# Main.net
KiCad netlist of a schematic drawn in Altium Designer
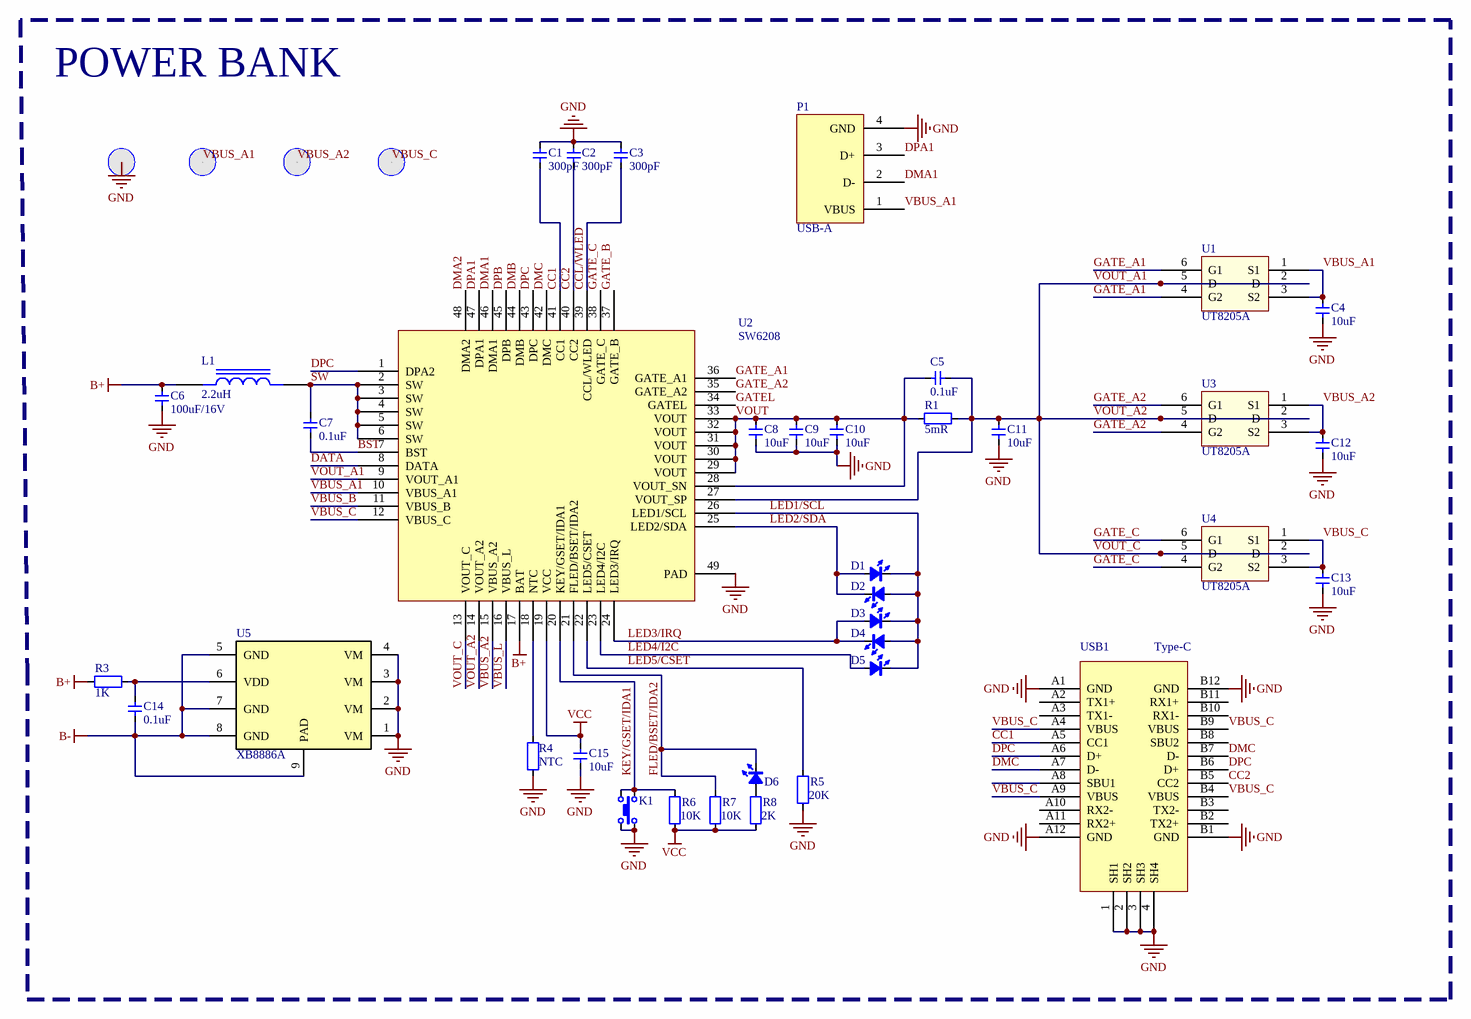
[diagram p0: Main.SchDoc]

(export (version "E")
  (design (tool "Eeschema 10.0.6"))
  (components
    (comp (ref "C1")
      (value "300pF")
      (footprint "XG_电容(SMC):0805C")
      (description "Capacitor")
      (libsource (lib "MyPcbLib") (part "电容-0402"))
    )
    (comp (ref "C2")
      (value "300pF")
      (footprint "XG_电容(SMC):0805C")
      (description "Capacitor")
      (libsource (lib "MyPcbLib") (part "电容-0402"))
    )
    (comp (ref "C3")
      (value "300pF")
      (footprint "XG_电容(SMC):0805C")
      (description "Capacitor")
      (libsource (lib "MyPcbLib") (part "电容-0402"))
    )
    (comp (ref "C4")
      (value "10uF")
      (footprint "SW6208Power_Bank:0603-CAP")
      (description "Capacitor")
      (libsource (lib "MyPcbLib") (part "电容-0603"))
    )
    (comp (ref "C5")
      (value "0.1uF")
      (footprint "XG_电容(SMC):0805C")
      (description "Capacitor")
      (libsource (lib "MyPcbLib") (part "电容-0402"))
    )
    (comp (ref "C6")
      (value "100uF/16V")
      (footprint "SW6208Power_Bank:1206-CAP")
      (description "Capacitor")
      (libsource (lib "MyPcbLib") (part "电容-1206"))
    )
    (comp (ref "C7")
      (value "0.1uF")
      (footprint "XG_电容(SMC):0805C")
      (description "Capacitor")
      (libsource (lib "MyPcbLib") (part "电容-0402"))
    )
    (comp (ref "C8")
      (value "10uF")
      (footprint "SW6208Power_Bank:0603-CAP")
      (description "Capacitor")
      (libsource (lib "MyPcbLib") (part "电容-0603"))
    )
    (comp (ref "C9")
      (value "10uF")
      (footprint "SW6208Power_Bank:0603-CAP")
      (description "Capacitor")
      (libsource (lib "MyPcbLib") (part "电容-0603"))
    )
    (comp (ref "C10")
      (value "10uF")
      (footprint "SW6208Power_Bank:0603-CAP")
      (description "Capacitor")
      (libsource (lib "MyPcbLib") (part "电容-0603"))
    )
    (comp (ref "C11")
      (value "10uF")
      (footprint "SW6208Power_Bank:0603-CAP")
      (description "Capacitor")
      (libsource (lib "MyPcbLib") (part "电容-0603"))
    )
    (comp (ref "C12")
      (value "10uF")
      (footprint "SW6208Power_Bank:0603-CAP")
      (description "Capacitor")
      (libsource (lib "MyPcbLib") (part "电容-0603"))
    )
    (comp (ref "C13")
      (value "10uF")
      (footprint "SW6208Power_Bank:0603-CAP")
      (description "Capacitor")
      (libsource (lib "MyPcbLib") (part "电容-0603"))
    )
    (comp (ref "C14")
      (value "0.1uF")
      (footprint "XG_电容(SMC):0805C")
      (description "Capacitor")
      (libsource (lib "MyPcbLib") (part "电容-0402"))
    )
    (comp (ref "C15")
      (value "10uF")
      (footprint "SW6208Power_Bank:0603-CAP")
      (description "Capacitor")
      (libsource (lib "MyPcbLib") (part "电容-0603"))
    )
    (comp (ref "D1")
      (value "color?")
      (footprint "XG_LED:LED0805R")
      (description "LED")
      (libsource (lib "KitSprout") (part "LED_0402"))
    )
    (comp (ref "D2")
      (value "color?")
      (footprint "XG_LED:LED0805R")
      (description "LED")
      (libsource (lib "") (part "LED_0402_1"))
    )
    (comp (ref "D3")
      (value "color?")
      (footprint "XG_LED:LED0805R")
      (description "LED")
      (libsource (lib "KitSprout") (part "LED_0402"))
    )
    (comp (ref "D4")
      (value "color?")
      (footprint "XG_LED:LED0805R")
      (description "LED")
      (libsource (lib "") (part "LED_0402_1"))
    )
    (comp (ref "D5")
      (value "color?")
      (footprint "XG_LED:LED0805R")
      (description "LED")
      (libsource (lib "KitSprout") (part "LED_0402"))
    )
    (comp (ref "D6")
      (value "color?")
      (footprint "XG_LED:LED0805R")
      (description "LED")
      (libsource (lib "") (part "LED_0402_2"))
    )
    (comp (ref "K1")
      (value "TACT 4P")
      (footprint "SW6208Power_Bank:ButtonTACT_3.5*3.55_90")
      (description "Button")
      (libsource (lib "KitSprout") (part "ButtonTACT"))
    )
    (comp (ref "L1")
      (value "2.2uH")
      (footprint "SW6208Power_Bank:IND_1040")
      (description "Fixed Inductors 4.7uH 30% SMD 1240")
      (fields (field (name "MF") "Bourns") (field (name "MP") "SRR1240-4R7Y"))
      (libsource (lib "mLib") (part "电感-1040"))
    )
    (comp (ref "P1")
      (value "USB-A")
      (footprint "SW6208Power_Bank:USB-Short")
      (libsource (lib "MyPcbLib") (part "USB-A"))
    )
    (comp (ref "R1")
      (value "5mR")
      (footprint "SW6208Power_Bank:1206-RES")
      (description "Resistor")
      (libsource (lib "MyPcbLib") (part "电阻-1206"))
    )
    (comp (ref "R3")
      (value "1K")
      (footprint "XG_电阻(SMC):0805R")
      (description "Resistor")
      (libsource (lib "") (part "电阻-0402_1"))
    )
    (comp (ref "R4")
      (value "NTC")
      (footprint "SW6208Power_Bank:0805-L")
      (description "Resistor")
      (libsource (lib "MyPcbLib") (part "电阻-0805"))
    )
    (comp (ref "R5")
      (value "20K")
      (footprint "XG_电阻(SMC):0805R")
      (description "Resistor")
      (libsource (lib "MyPcbLib") (part "电阻-0402"))
    )
    (comp (ref "R6")
      (value "10K")
      (footprint "XG_电阻(SMC):0805R")
      (description "Resistor")
      (libsource (lib "MyPcbLib") (part "电阻-0402"))
    )
    (comp (ref "R7")
      (value "10K")
      (footprint "XG_电阻(SMC):0805R")
      (description "Resistor")
      (libsource (lib "MyPcbLib") (part "电阻-0402"))
    )
    (comp (ref "R8")
      (value "2K")
      (footprint "XG_电阻(SMC):0805R")
      (description "Resistor")
      (libsource (lib "MyPcbLib") (part "电阻-0402"))
    )
    (comp (ref "T1")
      (value "测试点")
      (footprint "SW6208Power_Bank:TEST_PT")
      (libsource (lib "MyPcbLib") (part "测试点"))
    )
    (comp (ref "T2")
      (value "测试点")
      (footprint "SW6208Power_Bank:TEST_PT")
      (libsource (lib "MyPcbLib") (part "测试点"))
    )
    (comp (ref "T3")
      (value "测试点")
      (footprint "SW6208Power_Bank:TEST_PT")
      (libsource (lib "MyPcbLib") (part "测试点"))
    )
    (comp (ref "T4")
      (value "测试点")
      (footprint "SW6208Power_Bank:TEST_PT")
      (libsource (lib "MyPcbLib") (part "测试点"))
    )
    (comp (ref "U1")
      (value "UT8205A")
      (footprint "SW6208Power_Bank:SOT23-6")
      (libsource (lib "mLib") (part "UT8205A"))
    )
    (comp (ref "U2")
      (value "SW6208")
      (footprint "SW6208Power_Bank:QFN-48_6x6")
      (description "充电宝芯片")
      (libsource (lib "mLib") (part "SW6208"))
    )
    (comp (ref "U3")
      (value "UT8205A")
      (footprint "SW6208Power_Bank:SOT23-6")
      (libsource (lib "mLib") (part "UT8205A"))
    )
    (comp (ref "U4")
      (value "UT8205A")
      (footprint "SW6208Power_Bank:SOT23-6")
      (libsource (lib "mLib") (part "UT8205A"))
    )
    (comp (ref "U5")
      (value "XB8886A")
      (footprint "SW6208Power_Bank:SO-8-PAD")
      (fields (field (name "MF") "Texas Instruments") (field (name "MP") "NE5532D"))
      (libsource (lib "mLib") (part "XB8886A"))
    )
    (comp (ref "USB1")
      (value "Type-C")
      (footprint "SW6208Power_Bank:Type-C-TOP")
      (libsource (lib "MyPcbLib") (part "USB-Type-C-TOP"))
    )
  )
  (nets
    (net (code "1") (name "/BST") (class "Default")
      (node (ref "C7") (pin "2") (pinfunction "2_2") (pintype "passive"))
      (node (ref "U2") (pin "7") (pinfunction "BST_7") (pintype "passive"))
    )
    (net (code "2") (name "/CC1") (class "Default")
      (node (ref "C1") (pin "2") (pinfunction "2_2") (pintype "passive"))
      (node (ref "U2") (pin "41") (pinfunction "CC1_41") (pintype "passive"))
      (node (ref "USB1") (pin "A5") (pinfunction "CC1_A5") (pintype "passive"))
    )
    (net (code "3") (name "/CC2") (class "Default")
      (node (ref "C2") (pin "2") (pinfunction "2_2") (pintype "passive"))
      (node (ref "U2") (pin "40") (pinfunction "CC2_40") (pintype "passive"))
      (node (ref "USB1") (pin "B5") (pinfunction "CC2_B5") (pintype "passive"))
    )
    (net (code "4") (name "/CCL{slash}WLED") (class "Default")
      (node (ref "C3") (pin "2") (pinfunction "2_2") (pintype "passive"))
      (node (ref "U2") (pin "39") (pinfunction "CCL/WLED_39") (pintype "passive"))
    )
    (net (code "5") (name "/DATA") (class "Default")
      (node (ref "U2") (pin "8") (pinfunction "DATA_8") (pintype "passive"))
    )
    (net (code "6") (name "/DMA1") (class "Default")
      (node (ref "P1") (pin "2") (pinfunction "D-_2") (pintype "passive"))
      (node (ref "U2") (pin "46") (pinfunction "DMA1_46") (pintype "passive"))
    )
    (net (code "7") (name "/DMA2") (class "Default")
      (node (ref "U2") (pin "48") (pinfunction "DMA2_48") (pintype "passive"))
    )
    (net (code "8") (name "/DMB") (class "Default")
      (node (ref "U2") (pin "44") (pinfunction "DMB_44") (pintype "passive"))
    )
    (net (code "9") (name "/DMC") (class "Default")
      (node (ref "U2") (pin "42") (pinfunction "DMC_42") (pintype "passive"))
      (node (ref "USB1") (pin "A7") (pinfunction "D-_A7") (pintype "passive"))
      (node (ref "USB1") (pin "B7") (pinfunction "D-_B7") (pintype "passive"))
    )
    (net (code "10") (name "/DPA1") (class "Default")
      (node (ref "P1") (pin "3") (pinfunction "D+_3") (pintype "passive"))
      (node (ref "U2") (pin "47") (pinfunction "DPA1_47") (pintype "passive"))
    )
    (net (code "11") (name "/DPB") (class "Default")
      (node (ref "U2") (pin "45") (pinfunction "DPB_45") (pintype "passive"))
    )
    (net (code "12") (name "/DPC") (class "Default")
      (node (ref "U2") (pin "1") (pinfunction "DPA2_1") (pintype "passive"))
      (node (ref "U2") (pin "43") (pinfunction "DPC_43") (pintype "passive"))
      (node (ref "USB1") (pin "A6") (pinfunction "D+_A6") (pintype "passive"))
      (node (ref "USB1") (pin "B6") (pinfunction "D+_B6") (pintype "passive"))
    )
    (net (code "13") (name "/FLED{slash}BSET{slash}IDA2") (class "Default")
      (node (ref "D6") (pin "2") (pinfunction "K_2") (pintype "passive"))
      (node (ref "R7") (pin "1") (pinfunction "1_1") (pintype "passive"))
      (node (ref "U2") (pin "21") (pinfunction "FLED/BSET/IDA2_21") (pintype "passive"))
    )
    (net (code "14") (name "/GATEL") (class "Default")
      (node (ref "U2") (pin "34") (pinfunction "GATEL_34") (pintype "passive"))
    )
    (net (code "15") (name "/GATE_A1") (class "Default")
      (node (ref "U1") (pin "4") (pinfunction "G2_4") (pintype "passive"))
      (node (ref "U1") (pin "6") (pinfunction "G1_6") (pintype "passive"))
      (node (ref "U2") (pin "36") (pinfunction "GATE_A1_36") (pintype "passive"))
    )
    (net (code "16") (name "/GATE_A2") (class "Default")
      (node (ref "U2") (pin "35") (pinfunction "GATE_A2_35") (pintype "passive"))
      (node (ref "U3") (pin "4") (pinfunction "G2_4") (pintype "passive"))
      (node (ref "U3") (pin "6") (pinfunction "G1_6") (pintype "passive"))
    )
    (net (code "17") (name "/GATE_B") (class "Default")
      (node (ref "U2") (pin "37") (pinfunction "GATE_B_37") (pintype "passive"))
    )
    (net (code "18") (name "/GATE_C") (class "Default")
      (node (ref "U2") (pin "38") (pinfunction "GATE_C_38") (pintype "passive"))
      (node (ref "U4") (pin "4") (pinfunction "G2_4") (pintype "passive"))
      (node (ref "U4") (pin "6") (pinfunction "G1_6") (pintype "passive"))
    )
    (net (code "19") (name "/KEY{slash}GSET{slash}IDA1") (class "Default")
      (node (ref "K1") (pin "2") (pinfunction "2_2") (pintype "passive"))
      (node (ref "K1") (pin "4") (pinfunction "4_4") (pintype "passive"))
      (node (ref "R6") (pin "1") (pinfunction "1_1") (pintype "passive"))
      (node (ref "U2") (pin "20") (pinfunction "KEY/GSET/IDA1_20") (pintype "passive"))
    )
    (net (code "20") (name "/LED1{slash}SCL") (class "Default")
      (node (ref "D1") (pin "2") (pinfunction "K_2") (pintype "passive"))
      (node (ref "D2") (pin "1") (pinfunction "A_1") (pintype "passive"))
      (node (ref "D3") (pin "2") (pinfunction "K_2") (pintype "passive"))
      (node (ref "D4") (pin "1") (pinfunction "A_1") (pintype "passive"))
      (node (ref "D5") (pin "2") (pinfunction "K_2") (pintype "passive"))
      (node (ref "U2") (pin "26") (pinfunction "LED1/SCL_26") (pintype "passive"))
    )
    (net (code "21") (name "/LED2{slash}SDA") (class "Default")
      (node (ref "D1") (pin "1") (pinfunction "A_1") (pintype "passive"))
      (node (ref "D2") (pin "2") (pinfunction "K_2") (pintype "passive"))
      (node (ref "U2") (pin "25") (pinfunction "LED2/SDA_25") (pintype "passive"))
    )
    (net (code "22") (name "/LED3{slash}IRQ") (class "Default")
      (node (ref "D3") (pin "1") (pinfunction "A_1") (pintype "passive"))
      (node (ref "D4") (pin "2") (pinfunction "K_2") (pintype "passive"))
      (node (ref "U2") (pin "24") (pinfunction "LED3/IRQ_24") (pintype "passive"))
    )
    (net (code "23") (name "/LED4{slash}I2C") (class "Default")
      (node (ref "D5") (pin "1") (pinfunction "A_1") (pintype "passive"))
      (node (ref "U2") (pin "23") (pinfunction "LED4/I2C_23") (pintype "passive"))
    )
    (net (code "24") (name "/LED5{slash}CSET") (class "Default")
      (node (ref "R5") (pin "1") (pinfunction "1_1") (pintype "passive"))
      (node (ref "U2") (pin "22") (pinfunction "LED5/CSET_22") (pintype "passive"))
    )
    (net (code "25") (name "/SW") (class "Default")
      (node (ref "C7") (pin "1") (pinfunction "1_1") (pintype "passive"))
      (node (ref "L1") (pin "2") (pinfunction "2_2") (pintype "passive"))
      (node (ref "U2") (pin "2") (pinfunction "SW_2") (pintype "passive"))
      (node (ref "U2") (pin "3") (pinfunction "SW_3") (pintype "passive"))
      (node (ref "U2") (pin "4") (pinfunction "SW_4") (pintype "passive"))
      (node (ref "U2") (pin "5") (pinfunction "SW_5") (pintype "passive"))
      (node (ref "U2") (pin "6") (pinfunction "SW_6") (pintype "passive"))
    )
    (net (code "26") (name "/VBUS_A1") (class "Default")
      (node (ref "C4") (pin "2") (pinfunction "2_2") (pintype "passive"))
      (node (ref "P1") (pin "1") (pinfunction "VBUS_1") (pintype "passive"))
      (node (ref "T2") (pin "0") (pinfunction "0_0") (pintype "passive"))
      (node (ref "U1") (pin "1") (pinfunction "S1_1") (pintype "passive"))
      (node (ref "U1") (pin "3") (pinfunction "S2_3") (pintype "passive"))
      (node (ref "U2") (pin "10") (pinfunction "VBUS_A1_10") (pintype "passive"))
    )
    (net (code "27") (name "/VBUS_A2") (class "Default")
      (node (ref "C12") (pin "2") (pinfunction "2_2") (pintype "passive"))
      (node (ref "T3") (pin "0") (pinfunction "0_0") (pintype "passive"))
      (node (ref "U2") (pin "15") (pinfunction "VBUS_A2_15") (pintype "passive"))
      (node (ref "U3") (pin "1") (pinfunction "S1_1") (pintype "passive"))
      (node (ref "U3") (pin "3") (pinfunction "S2_3") (pintype "passive"))
    )
    (net (code "28") (name "/VBUS_B") (class "Default")
      (node (ref "U2") (pin "11") (pinfunction "VBUS_B_11") (pintype "passive"))
    )
    (net (code "29") (name "/VBUS_C") (class "Default")
      (node (ref "C13") (pin "2") (pinfunction "2_2") (pintype "passive"))
      (node (ref "T4") (pin "0") (pinfunction "0_0") (pintype "passive"))
      (node (ref "U2") (pin "12") (pinfunction "VBUS_C_12") (pintype "passive"))
      (node (ref "U4") (pin "1") (pinfunction "S1_1") (pintype "passive"))
      (node (ref "U4") (pin "3") (pinfunction "S2_3") (pintype "passive"))
      (node (ref "USB1") (pin "A4") (pinfunction "VBUS_A4") (pintype "passive"))
      (node (ref "USB1") (pin "A9") (pinfunction "VBUS_A9") (pintype "passive"))
      (node (ref "USB1") (pin "B4") (pinfunction "VBUS_B4") (pintype "passive"))
      (node (ref "USB1") (pin "B9") (pinfunction "VBUS_B9") (pintype "passive"))
    )
    (net (code "30") (name "/VBUS_L") (class "Default")
      (node (ref "U2") (pin "16") (pinfunction "VBUS_L_16") (pintype "passive"))
    )
    (net (code "31") (name "/VOUT") (class "Default")
      (node (ref "C10") (pin "2") (pinfunction "2_2") (pintype "passive"))
      (node (ref "C5") (pin "1") (pinfunction "1_1") (pintype "passive"))
      (node (ref "C8") (pin "2") (pinfunction "2_2") (pintype "passive"))
      (node (ref "C9") (pin "2") (pinfunction "2_2") (pintype "passive"))
      (node (ref "R1") (pin "1") (pinfunction "1_1") (pintype "passive"))
      (node (ref "U2") (pin "28") (pinfunction "VOUT_SN_28") (pintype "passive"))
      (node (ref "U2") (pin "29") (pinfunction "VOUT_29") (pintype "passive"))
      (node (ref "U2") (pin "30") (pinfunction "VOUT_30") (pintype "passive"))
      (node (ref "U2") (pin "31") (pinfunction "VOUT_31") (pintype "passive"))
      (node (ref "U2") (pin "32") (pinfunction "VOUT_32") (pintype "passive"))
      (node (ref "U2") (pin "33") (pinfunction "VOUT_33") (pintype "passive"))
    )
    (net (code "32") (name "/VOUT_A1") (class "Default")
      (node (ref "C11") (pin "2") (pinfunction "2_2") (pintype "passive"))
      (node (ref "C5") (pin "2") (pinfunction "2_2") (pintype "passive"))
      (node (ref "R1") (pin "2") (pinfunction "2_2") (pintype "passive"))
      (node (ref "U1") (pin "2") (pinfunction "D_2") (pintype "passive"))
      (node (ref "U1") (pin "5") (pinfunction "D_5") (pintype "passive"))
      (node (ref "U2") (pin "13") (pinfunction "VOUT_C_13") (pintype "passive"))
      (node (ref "U2") (pin "14") (pinfunction "VOUT_A2_14") (pintype "passive"))
      (node (ref "U2") (pin "27") (pinfunction "VOUT_SP_27") (pintype "passive"))
      (node (ref "U2") (pin "9") (pinfunction "VOUT_A1_9") (pintype "passive"))
      (node (ref "U3") (pin "2") (pinfunction "D_2") (pintype "passive"))
      (node (ref "U3") (pin "5") (pinfunction "D_5") (pintype "passive"))
      (node (ref "U4") (pin "2") (pinfunction "D_2") (pintype "passive"))
      (node (ref "U4") (pin "5") (pinfunction "D_5") (pintype "passive"))
    )
    (net (code "33") (name "B+") (class "Default")
      (node (ref "C6") (pin "2") (pinfunction "2_2") (pintype "passive"))
      (node (ref "L1") (pin "1") (pinfunction "1_1") (pintype "passive"))
      (node (ref "R3") (pin "2") (pinfunction "2_2") (pintype "passive"))
      (node (ref "U2") (pin "17") (pinfunction "BAT_17") (pintype "passive"))
    )
    (net (code "34") (name "B-") (class "Default")
      (node (ref "C14") (pin "2") (pinfunction "2_2") (pintype "passive"))
      (node (ref "U5") (pin "5") (pinfunction "GND_5") (pintype "passive"))
      (node (ref "U5") (pin "7") (pinfunction "GND_7") (pintype "passive"))
      (node (ref "U5") (pin "8") (pinfunction "GND_8") (pintype "passive"))
      (node (ref "U5") (pin "9") (pinfunction "PAD_9") (pintype "passive"))
    )
    (net (code "35") (name "GND") (class "Default")
      (node (ref "C1") (pin "1") (pinfunction "1_1") (pintype "passive"))
      (node (ref "C10") (pin "1") (pinfunction "1_1") (pintype "passive"))
      (node (ref "C11") (pin "1") (pinfunction "1_1") (pintype "passive"))
      (node (ref "C12") (pin "1") (pinfunction "1_1") (pintype "passive"))
      (node (ref "C13") (pin "1") (pinfunction "1_1") (pintype "passive"))
      (node (ref "C15") (pin "1") (pinfunction "1_1") (pintype "passive"))
      (node (ref "C2") (pin "1") (pinfunction "1_1") (pintype "passive"))
      (node (ref "C3") (pin "1") (pinfunction "1_1") (pintype "passive"))
      (node (ref "C4") (pin "1") (pinfunction "1_1") (pintype "passive"))
      (node (ref "C6") (pin "1") (pinfunction "1_1") (pintype "passive"))
      (node (ref "C8") (pin "1") (pinfunction "1_1") (pintype "passive"))
      (node (ref "C9") (pin "1") (pinfunction "1_1") (pintype "passive"))
      (node (ref "K1") (pin "1") (pinfunction "1_1") (pintype "passive"))
      (node (ref "K1") (pin "3") (pinfunction "3_3") (pintype "passive"))
      (node (ref "P1") (pin "4") (pinfunction "GND_4") (pintype "passive"))
      (node (ref "R4") (pin "1") (pinfunction "1_1") (pintype "passive"))
      (node (ref "R5") (pin "2") (pinfunction "2_2") (pintype "passive"))
      (node (ref "T1") (pin "0") (pinfunction "0_0") (pintype "passive"))
      (node (ref "U2") (pin "49") (pinfunction "PAD_49") (pintype "passive"))
      (node (ref "U5") (pin "1") (pinfunction "VM_1") (pintype "passive"))
      (node (ref "U5") (pin "2") (pinfunction "VM_2") (pintype "passive"))
      (node (ref "U5") (pin "3") (pinfunction "VM_3") (pintype "passive"))
      (node (ref "U5") (pin "4") (pinfunction "VM_4") (pintype "passive"))
      (node (ref "USB1") (pin "1") (pinfunction "SH1_1") (pintype "passive"))
      (node (ref "USB1") (pin "2") (pinfunction "SH2_2") (pintype "passive"))
      (node (ref "USB1") (pin "3") (pinfunction "SH3_3") (pintype "passive"))
      (node (ref "USB1") (pin "4") (pinfunction "SH4_4") (pintype "passive"))
      (node (ref "USB1") (pin "A1") (pinfunction "GND_A1") (pintype "passive"))
      (node (ref "USB1") (pin "A12") (pinfunction "GND_A12") (pintype "passive"))
      (node (ref "USB1") (pin "B1") (pinfunction "GND_B1") (pintype "passive"))
      (node (ref "USB1") (pin "B12") (pinfunction "GND_B12") (pintype "passive"))
    )
    (net (code "36") (name "Net-(D6-A)") (class "Default")
      (node (ref "D6") (pin "1") (pinfunction "A_1") (pintype "passive"))
      (node (ref "R8") (pin "1") (pinfunction "1_1") (pintype "passive"))
    )
    (net (code "37") (name "Net-(U2-NTC)") (class "Default")
      (node (ref "R4") (pin "2") (pinfunction "2_2") (pintype "passive"))
      (node (ref "U2") (pin "18") (pinfunction "NTC_18") (pintype "passive"))
    )
    (net (code "38") (name "Net-(U5-VDD)") (class "Default")
      (node (ref "C14") (pin "1") (pinfunction "1_1") (pintype "passive"))
      (node (ref "R3") (pin "1") (pinfunction "1_1") (pintype "passive"))
      (node (ref "U5") (pin "6") (pinfunction "VDD_6") (pintype "passive"))
    )
    (net (code "39") (name "VCC") (class "Default")
      (node (ref "C15") (pin "2") (pinfunction "2_2") (pintype "passive"))
      (node (ref "R6") (pin "2") (pinfunction "2_2") (pintype "passive"))
      (node (ref "R7") (pin "2") (pinfunction "2_2") (pintype "passive"))
      (node (ref "R8") (pin "2") (pinfunction "2_2") (pintype "passive"))
      (node (ref "U2") (pin "19") (pinfunction "VCC_19") (pintype "passive"))
    )
    (net (code "40") (name "unconnected-(USB1-RX1+-PadB11)") (class "Default")
      (node (ref "USB1") (pin "B11") (pinfunction "RX1+_B11") (pintype "passive"))
    )
    (net (code "41") (name "unconnected-(USB1-RX1--PadB10)") (class "Default")
      (node (ref "USB1") (pin "B10") (pinfunction "RX1-_B10") (pintype "passive"))
    )
    (net (code "42") (name "unconnected-(USB1-RX2+-PadA11)") (class "Default")
      (node (ref "USB1") (pin "A11") (pinfunction "RX2+_A11") (pintype "passive"))
    )
    (net (code "43") (name "unconnected-(USB1-RX2--PadA10)") (class "Default")
      (node (ref "USB1") (pin "A10") (pinfunction "RX2-_A10") (pintype "passive"))
    )
    (net (code "44") (name "unconnected-(USB1-SBU1-PadA8)") (class "Default")
      (node (ref "USB1") (pin "A8") (pinfunction "SBU1_A8") (pintype "passive"))
    )
    (net (code "45") (name "unconnected-(USB1-SBU2-PadB8)") (class "Default")
      (node (ref "USB1") (pin "B8") (pinfunction "SBU2_B8") (pintype "passive"))
    )
    (net (code "46") (name "unconnected-(USB1-TX1+-PadA2)") (class "Default")
      (node (ref "USB1") (pin "A2") (pinfunction "TX1+_A2") (pintype "passive"))
    )
    (net (code "47") (name "unconnected-(USB1-TX1--PadA3)") (class "Default")
      (node (ref "USB1") (pin "A3") (pinfunction "TX1-_A3") (pintype "passive"))
    )
    (net (code "48") (name "unconnected-(USB1-TX2+-PadB2)") (class "Default")
      (node (ref "USB1") (pin "B2") (pinfunction "TX2+_B2") (pintype "passive"))
    )
    (net (code "49") (name "unconnected-(USB1-TX2--PadB3)") (class "Default")
      (node (ref "USB1") (pin "B3") (pinfunction "TX2-_B3") (pintype "passive"))
    )
  )
)
